# main.net
KiCad netlist of a schematic drawn in EAGLE
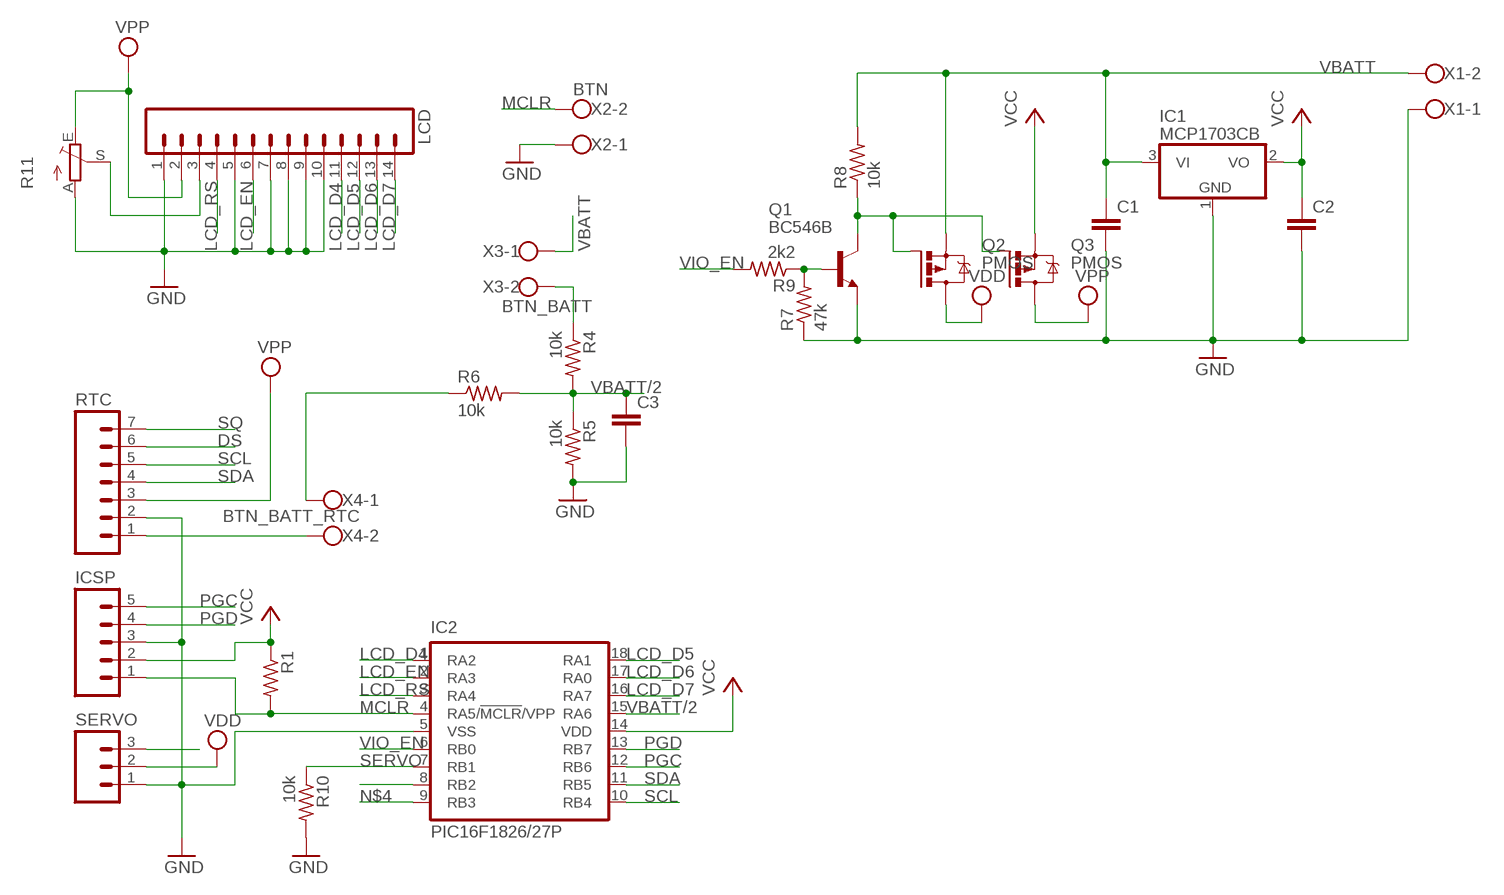
[diagram p0: schematic, sheet 1]

(export (version "E")
  (design (tool "Eeschema 10.0.6"))
  (components
    (comp (ref "C1")
      (value "C-EUC0805K")
      (footprint "eagle-import:C0805K")
      (libsource (lib "eagle-import") (part "C-EUC0805K"))
    )
    (comp (ref "C2")
      (value "C-EUC0805K")
      (footprint "eagle-import:C0805K")
      (libsource (lib "eagle-import") (part "C-EUC0805K"))
    )
    (comp (ref "C3")
      (value "C-EUC0805K")
      (footprint "eagle-import:C0805K")
      (libsource (lib "eagle-import") (part "C-EUC0805K"))
    )
    (comp (ref "IC1")
      (value "MCP1703CB")
      (footprint "eagle-import:SOT23")
      (libsource (lib "eagle-import") (part "MCP1703CB"))
    )
    (comp (ref "IC2")
      (value "PIC16F1826/27P")
      (footprint "eagle-import:DIL18")
      (libsource (lib "eagle-import") (part "PIC16F1826/27P"))
    )
    (comp (ref "ICSP")
      (value "M05")
      (footprint "eagle-import:05P")
      (libsource (lib "eagle-import") (part "M05"))
    )
    (comp (ref "LCD")
      (value "M14")
      (footprint "eagle-import:14P")
      (libsource (lib "eagle-import") (part "M14"))
    )
    (comp (ref "Q1")
      (value "BC546B")
      (footprint "eagle-import:TO92-EBC")
      (libsource (lib "eagle-import") (part "BC546B"))
    )
    (comp (ref "Q2")
      (value "PMOS")
      (footprint "eagle-import:MICRO3")
      (libsource (lib "eagle-import") (part "IRLML5203"))
    )
    (comp (ref "Q3")
      (value "PMOS")
      (footprint "eagle-import:MICRO3")
      (libsource (lib "eagle-import") (part "IRLML5203"))
    )
    (comp (ref "R1")
      (value "R-US_0207/10")
      (footprint "eagle-import:0207_10")
      (libsource (lib "eagle-import") (part "R-US_0207/10"))
    )
    (comp (ref "R4")
      (value "10k")
      (footprint "eagle-import:R1005")
      (libsource (lib "eagle-import") (part "R-US_R1005"))
    )
    (comp (ref "R5")
      (value "10k")
      (footprint "eagle-import:R1005")
      (libsource (lib "eagle-import") (part "R-US_R1005"))
    )
    (comp (ref "R6")
      (value "10k")
      (footprint "eagle-import:R1005")
      (libsource (lib "eagle-import") (part "R-US_R1005"))
    )
    (comp (ref "R7")
      (value "47k")
      (footprint "eagle-import:R1005")
      (libsource (lib "eagle-import") (part "R-US_R1005"))
    )
    (comp (ref "R8")
      (value "10k")
      (footprint "eagle-import:R1005")
      (libsource (lib "eagle-import") (part "R-US_R1005"))
    )
    (comp (ref "R9")
      (value "2k2")
      (footprint "eagle-import:R1005")
      (libsource (lib "eagle-import") (part "R-US_R1005"))
    )
    (comp (ref "R10")
      (value "10k")
      (footprint "eagle-import:R1005")
      (libsource (lib "eagle-import") (part "R-US_R1005"))
    )
    (comp (ref "R11")
      (value "TRIM_EU-LI10")
      (footprint "eagle-import:LI10")
      (libsource (lib "eagle-import") (part "TRIM_EU-LI10"))
    )
    (comp (ref "RTC")
      (value "M07")
      (footprint "eagle-import:07P")
      (libsource (lib "eagle-import") (part "M07"))
    )
    (comp (ref "SERVO")
      (value "M03")
      (footprint "eagle-import:03P")
      (libsource (lib "eagle-import") (part "M03"))
    )
    (comp (ref "X1")
      (value "W237-102")
      (footprint "eagle-import:W237-102")
      (fields (field (name "MPN") "237-102"))
      (libsource (lib "eagle-import") (part "W237-102"))
    )
    (comp (ref "X2")
      (value "BTN")
      (footprint "eagle-import:W237-102")
      (fields (field (name "MPN") "237-102"))
      (libsource (lib "eagle-import") (part "W237-102"))
    )
    (comp (ref "X3")
      (value "BTN_BATT")
      (footprint "eagle-import:W237-102")
      (fields
        (field (name "MPN") "237-102")
        (field (name "MPN_1") "237-102")
        (field (name "OC_FARNELL") "unknown")
        (field (name "OC_NEWARK") "70K9898")
      )
      (libsource (lib "eagle-import") (part "W237-102"))
    )
    (comp (ref "X4")
      (value "BTN_BATT_RTC")
      (footprint "eagle-import:W237-102")
      (fields
        (field (name "MPN") "237-102")
        (field (name "MPN_1") "237-102")
        (field (name "OC_FARNELL") "unknown")
        (field (name "OC_NEWARK") "70K9898")
      )
      (libsource (lib "eagle-import") (part "W237-102"))
    )
  )
  (nets
    (net (code "1") (name "/DS") (class "Default")
      (node (ref "RTC") (pin "6") (pinfunction "6_6") (pintype "passive"))
    )
    (net (code "2") (name "/LCD_D4") (class "Default")
      (node (ref "IC2") (pin "1") (pinfunction "RA2_1") (pintype "bidirectional"))
      (node (ref "LCD") (pin "11") (pinfunction "11_11") (pintype "passive"))
    )
    (net (code "3") (name "/LCD_D5") (class "Default")
      (node (ref "IC2") (pin "18") (pinfunction "RA1_18") (pintype "bidirectional"))
      (node (ref "LCD") (pin "12") (pinfunction "12_12") (pintype "passive"))
    )
    (net (code "4") (name "/LCD_D6") (class "Default")
      (node (ref "IC2") (pin "17") (pinfunction "RA0_17") (pintype "bidirectional"))
      (node (ref "LCD") (pin "13") (pinfunction "13_13") (pintype "passive"))
    )
    (net (code "5") (name "/LCD_D7") (class "Default")
      (node (ref "IC2") (pin "16") (pinfunction "RA7_16") (pintype "bidirectional"))
      (node (ref "LCD") (pin "14") (pinfunction "14_14") (pintype "passive"))
    )
    (net (code "6") (name "/LCD_EN") (class "Default")
      (node (ref "IC2") (pin "2") (pinfunction "RA3_2") (pintype "bidirectional"))
      (node (ref "LCD") (pin "6") (pinfunction "6_6") (pintype "passive"))
    )
    (net (code "7") (name "/LCD_RS") (class "Default")
      (node (ref "IC2") (pin "3") (pinfunction "RA4_3") (pintype "bidirectional"))
      (node (ref "LCD") (pin "4") (pinfunction "4_4") (pintype "passive"))
    )
    (net (code "8") (name "/MCLR") (class "Default")
      (node (ref "IC2") (pin "4") (pinfunction "RA5/~{MCLR}/VPP_4") (pintype "bidirectional"))
      (node (ref "ICSP") (pin "1") (pinfunction "1_1") (pintype "passive"))
      (node (ref "R1") (pin "2") (pinfunction "2_2") (pintype "passive"))
      (node (ref "X2") (pin "2") (pinfunction "KL_2") (pintype "passive"))
    )
    (net (code "9") (name "/N$4") (class "Default")
      (node (ref "IC2") (pin "9") (pinfunction "RB3_9") (pintype "bidirectional"))
    )
    (net (code "10") (name "/PGC") (class "Default")
      (node (ref "IC2") (pin "12") (pinfunction "RB6_12") (pintype "bidirectional"))
      (node (ref "ICSP") (pin "5") (pinfunction "5_5") (pintype "passive"))
    )
    (net (code "11") (name "/PGD") (class "Default")
      (node (ref "IC2") (pin "13") (pinfunction "RB7_13") (pintype "bidirectional"))
      (node (ref "ICSP") (pin "4") (pinfunction "4_4") (pintype "passive"))
    )
    (net (code "12") (name "/SCL") (class "Default")
      (node (ref "IC2") (pin "10") (pinfunction "RB4_10") (pintype "bidirectional"))
      (node (ref "RTC") (pin "5") (pinfunction "5_5") (pintype "passive"))
    )
    (net (code "13") (name "/SDA") (class "Default")
      (node (ref "IC2") (pin "11") (pinfunction "RB5_11") (pintype "bidirectional"))
      (node (ref "RTC") (pin "4") (pinfunction "4_4") (pintype "passive"))
    )
    (net (code "14") (name "/SERVO") (class "Default")
      (node (ref "IC2") (pin "7") (pinfunction "RB1_7") (pintype "bidirectional"))
      (node (ref "R10") (pin "1") (pinfunction "1_1") (pintype "passive"))
      (node (ref "SERVO") (pin "3") (pinfunction "3_3") (pintype "passive"))
    )
    (net (code "15") (name "/SQ") (class "Default")
      (node (ref "RTC") (pin "7") (pinfunction "7_7") (pintype "passive"))
    )
    (net (code "16") (name "/VBATT") (class "Default")
      (node (ref "C1") (pin "1") (pinfunction "1_1") (pintype "passive"))
      (node (ref "IC1") (pin "3") (pinfunction "VI_3") (pintype "input"))
      (node (ref "Q2") (pin "2") (pinfunction "S_2") (pintype "passive"))
      (node (ref "R8") (pin "2") (pinfunction "2_2") (pintype "passive"))
      (node (ref "X1") (pin "2") (pinfunction "KL_2") (pintype "passive"))
      (node (ref "X3") (pin "1") (pinfunction "KL_1") (pintype "passive"))
    )
    (net (code "17") (name "/VBATT{slash}2") (class "Default")
      (node (ref "C3") (pin "1") (pinfunction "1_1") (pintype "passive"))
      (node (ref "IC2") (pin "15") (pinfunction "RA6_15") (pintype "bidirectional"))
      (node (ref "R4") (pin "2") (pinfunction "2_2") (pintype "passive"))
      (node (ref "R5") (pin "1") (pinfunction "1_1") (pintype "passive"))
      (node (ref "R6") (pin "2") (pinfunction "2_2") (pintype "passive"))
    )
    (net (code "18") (name "/VIO_EN") (class "Default")
      (node (ref "IC2") (pin "6") (pinfunction "RB0_6") (pintype "bidirectional"))
      (node (ref "R9") (pin "2") (pinfunction "2_2") (pintype "passive"))
    )
    (net (code "19") (name "GND") (class "Default")
      (node (ref "C1") (pin "2") (pinfunction "2_2") (pintype "passive"))
      (node (ref "C2") (pin "2") (pinfunction "2_2") (pintype "passive"))
      (node (ref "C3") (pin "2") (pinfunction "2_2") (pintype "passive"))
      (node (ref "IC1") (pin "1") (pinfunction "GND_1") (pintype "passive"))
      (node (ref "IC2") (pin "5") (pinfunction "VSS_5") (pintype "power_in"))
      (node (ref "ICSP") (pin "3") (pinfunction "3_3") (pintype "passive"))
      (node (ref "LCD") (pin "1") (pinfunction "1_1") (pintype "passive"))
      (node (ref "LCD") (pin "10") (pinfunction "10_10") (pintype "passive"))
      (node (ref "LCD") (pin "5") (pinfunction "5_5") (pintype "passive"))
      (node (ref "LCD") (pin "7") (pinfunction "7_7") (pintype "passive"))
      (node (ref "LCD") (pin "8") (pinfunction "8_8") (pintype "passive"))
      (node (ref "LCD") (pin "9") (pinfunction "9_9") (pintype "passive"))
      (node (ref "Q1") (pin "E") (pinfunction "E_E") (pintype "passive"))
      (node (ref "R10") (pin "2") (pinfunction "2_2") (pintype "passive"))
      (node (ref "R11") (pin "A") (pinfunction "A_A") (pintype "passive"))
      (node (ref "R5") (pin "2") (pinfunction "2_2") (pintype "passive"))
      (node (ref "R7") (pin "1") (pinfunction "1_1") (pintype "passive"))
      (node (ref "RTC") (pin "2") (pinfunction "2_2") (pintype "passive"))
      (node (ref "SERVO") (pin "1") (pinfunction "1_1") (pintype "passive"))
      (node (ref "X1") (pin "1") (pinfunction "KL_1") (pintype "passive"))
      (node (ref "X2") (pin "1") (pinfunction "KL_1") (pintype "passive"))
    )
    (net (code "20") (name "Net-(LCD-Pad3)") (class "Default")
      (node (ref "LCD") (pin "3") (pinfunction "3_3") (pintype "passive"))
      (node (ref "R11") (pin "S") (pinfunction "S_S") (pintype "passive"))
    )
    (net (code "21") (name "Net-(Q1-PadB)") (class "Default")
      (node (ref "Q1") (pin "B") (pinfunction "B_B") (pintype "passive"))
      (node (ref "R7") (pin "2") (pinfunction "2_2") (pintype "passive"))
      (node (ref "R9") (pin "1") (pinfunction "1_1") (pintype "passive"))
    )
    (net (code "22") (name "Net-(Q2-G)") (class "Default")
      (node (ref "Q1") (pin "C") (pinfunction "C_C") (pintype "passive"))
      (node (ref "Q2") (pin "1") (pinfunction "G_1") (pintype "passive"))
      (node (ref "Q3") (pin "1") (pinfunction "G_1") (pintype "passive"))
      (node (ref "R8") (pin "1") (pinfunction "1_1") (pintype "passive"))
    )
    (net (code "23") (name "Net-(X3B-KL)") (class "Default")
      (node (ref "R4") (pin "1") (pinfunction "1_1") (pintype "passive"))
      (node (ref "X3") (pin "2") (pinfunction "KL_2") (pintype "passive"))
    )
    (net (code "24") (name "Net-(X4A-KL)") (class "Default")
      (node (ref "R6") (pin "1") (pinfunction "1_1") (pintype "passive"))
      (node (ref "X4") (pin "1") (pinfunction "KL_1") (pintype "passive"))
    )
    (net (code "25") (name "Net-(X4B-KL)") (class "Default")
      (node (ref "RTC") (pin "1") (pinfunction "1_1") (pintype "passive"))
      (node (ref "X4") (pin "2") (pinfunction "KL_2") (pintype "passive"))
    )
    (net (code "26") (name "VCC") (class "Default")
      (node (ref "C2") (pin "1") (pinfunction "1_1") (pintype "passive"))
      (node (ref "IC1") (pin "2") (pinfunction "VO_2") (pintype "passive"))
      (node (ref "IC2") (pin "14") (pinfunction "VDD_14") (pintype "power_in"))
      (node (ref "ICSP") (pin "2") (pinfunction "2_2") (pintype "passive"))
      (node (ref "Q3") (pin "2") (pinfunction "S_2") (pintype "passive"))
      (node (ref "R1") (pin "1") (pinfunction "1_1") (pintype "passive"))
    )
    (net (code "27") (name "VDD") (class "Default")
      (node (ref "Q2") (pin "3") (pinfunction "D_3") (pintype "passive"))
      (node (ref "SERVO") (pin "2") (pinfunction "2_2") (pintype "passive"))
    )
    (net (code "28") (name "VPP") (class "Default")
      (node (ref "LCD") (pin "2") (pinfunction "2_2") (pintype "passive"))
      (node (ref "Q3") (pin "3") (pinfunction "D_3") (pintype "passive"))
      (node (ref "R11") (pin "E") (pinfunction "E_E") (pintype "passive"))
      (node (ref "RTC") (pin "3") (pinfunction "3_3") (pintype "passive"))
    )
    (net (code "29") (name "unconnected-(IC2-RB2-Pad8)") (class "Default")
      (node (ref "IC2") (pin "8") (pinfunction "RB2_8") (pintype "bidirectional"))
    )
  )
)
